# Thetis_RevD2_SCH.net
KiCad netlist of a schematic drawn in EAGLE
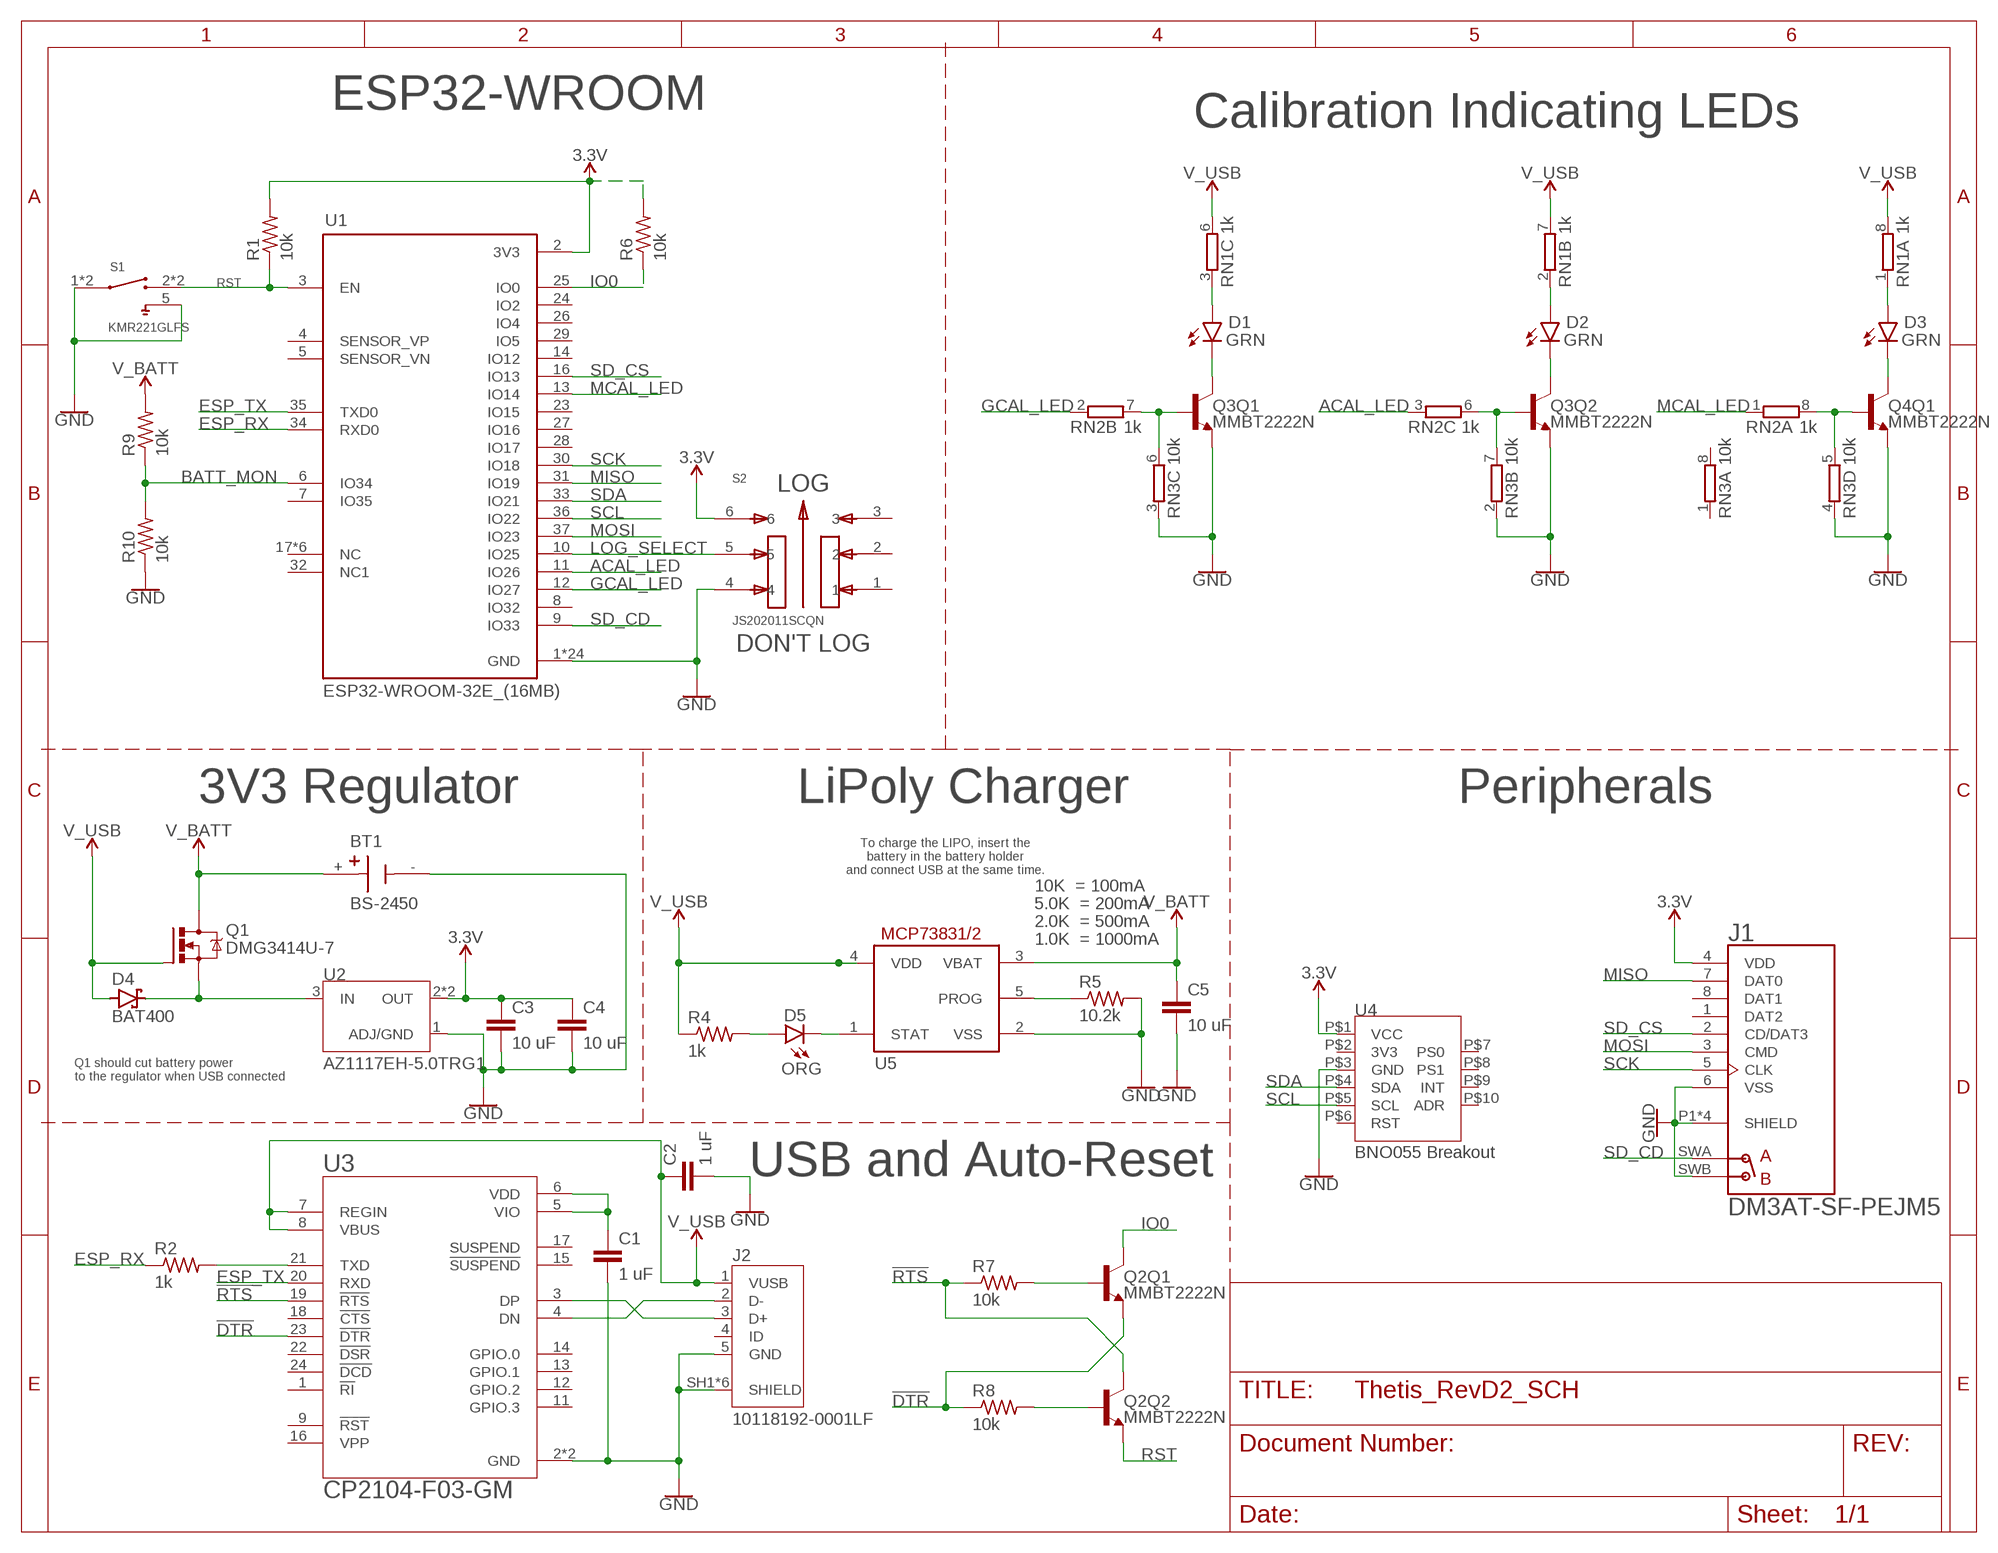
[diagram p0: schematic, sheet 1]

(export (version "E")
  (design (tool "Eeschema 10.0.6"))
  (components
    (comp (ref "BT1")
      (value "BS-2450")
      (footprint "eagle-import:BAT_BS-2450")
      (fields (field (name "MF") "MPD"))
      (libsource (lib "eagle-import") (part "BS-2450"))
    )
    (comp (ref "C1")
      (value "1 uF")
      (footprint "eagle-import:C0603")
      (libsource (lib "eagle-import") (part "C-EUC0603"))
    )
    (comp (ref "C2")
      (value "1 uF")
      (footprint "eagle-import:C0603")
      (libsource (lib "eagle-import") (part "C-EUC0603"))
    )
    (comp (ref "C3")
      (value "10 uF")
      (footprint "eagle-import:C0603")
      (libsource (lib "eagle-import") (part "C-EUC0603"))
    )
    (comp (ref "C4")
      (value "10 uF")
      (footprint "eagle-import:C0603")
      (libsource (lib "eagle-import") (part "C-EUC0603"))
    )
    (comp (ref "C5")
      (value "10 uF")
      (footprint "eagle-import:C0603")
      (libsource (lib "eagle-import") (part "C-EUC0603"))
    )
    (comp (ref "D1")
      (value "GRN")
      (footprint "eagle-import:LEDC1608X65N")
      (libsource (lib "eagle-import") (part "CHIP-ROUND-G_0603"))
    )
    (comp (ref "D2")
      (value "GRN")
      (footprint "eagle-import:LEDC1608X65N")
      (libsource (lib "eagle-import") (part "CHIP-ROUND-G_0603"))
    )
    (comp (ref "D3")
      (value "GRN")
      (footprint "eagle-import:LEDC1608X65N")
      (libsource (lib "eagle-import") (part "CHIP-ROUND-G_0603"))
    )
    (comp (ref "D4")
      (value "BAT400")
      (footprint "eagle-import:SOT23")
      (libsource (lib "eagle-import") (part "BAS40"))
    )
    (comp (ref "D5")
      (value "ORG")
      (footprint "eagle-import:LEDC1608X65N")
      (libsource (lib "eagle-import") (part "CHIP-ROUND-G_0603"))
    )
    (comp (ref "J1")
      (value "DM3AT-SF-PEJM5")
      (footprint "eagle-import:HRS_DM3AT-SF-PEJM5")
      (fields (field (name "MF") "Hirose"))
      (libsource (lib "eagle-import") (part "DM3AT-SF-PEJM5"))
    )
    (comp (ref "J2")
      (value "10118192-0001LF")
      (footprint "eagle-import:AMPHENOL_10118192-0001LF")
      (fields (field (name "MANUFACTURER") "Amphenol"))
      (libsource (lib "eagle-import") (part "10118192-0001LF"))
    )
    (comp (ref "Q1")
      (value "DMG3414U-7")
      (footprint "eagle-import:SOT23")
      (libsource (lib "eagle-import") (part "NMOSFETSOT23"))
    )
    (comp (ref "Q2")
      (value "MMBT2222N")
      (footprint "eagle-import:SC70-6")
      (libsource (lib "eagle-import") (part "TRANS_NPN_DUAL-MBT3904DW1T1"))
    )
    (comp (ref "Q3")
      (value "MMBT2222N")
      (footprint "eagle-import:SC70-6")
      (libsource (lib "eagle-import") (part "TRANS_NPN_DUAL-MBT3904DW1T1"))
    )
    (comp (ref "Q4")
      (value "MMBT2222N")
      (footprint "eagle-import:SC70-6")
      (libsource (lib "eagle-import") (part "TRANS_NPN_DUAL-MBT3904DW1T1"))
    )
    (comp (ref "R1")
      (value "10k")
      (footprint "eagle-import:R0603")
      (libsource (lib "eagle-import") (part "R-US_R0603"))
    )
    (comp (ref "R2")
      (value "1k")
      (footprint "eagle-import:R0603")
      (libsource (lib "eagle-import") (part "R-US_R0603"))
    )
    (comp (ref "R4")
      (value "1k")
      (footprint "eagle-import:R0603")
      (libsource (lib "eagle-import") (part "R-US_R0603"))
    )
    (comp (ref "R5")
      (value "10.2k")
      (footprint "eagle-import:R0603")
      (libsource (lib "eagle-import") (part "R-US_R0603"))
    )
    (comp (ref "R6")
      (value "10k")
      (footprint "eagle-import:R0603")
      (libsource (lib "eagle-import") (part "R-US_R0603"))
    )
    (comp (ref "R7")
      (value "10k")
      (footprint "eagle-import:R0603")
      (libsource (lib "eagle-import") (part "R-US_R0603"))
    )
    (comp (ref "R8")
      (value "10k")
      (footprint "eagle-import:R0603")
      (libsource (lib "eagle-import") (part "R-US_R0603"))
    )
    (comp (ref "R9")
      (value "10k")
      (footprint "eagle-import:R0603")
      (libsource (lib "eagle-import") (part "R-US_R0603"))
    )
    (comp (ref "R10")
      (value "10k")
      (footprint "eagle-import:R0603")
      (libsource (lib "eagle-import") (part "R-US_R0603"))
    )
    (comp (ref "RN1")
      (value "1k")
      (footprint "eagle-import:EXB28V")
      (libsource (lib "eagle-import") (part "4R-NEXB28V"))
    )
    (comp (ref "RN2")
      (value "1k")
      (footprint "eagle-import:EXB28V")
      (libsource (lib "eagle-import") (part "4R-NEXB28V"))
    )
    (comp (ref "RN3")
      (value "10k")
      (footprint "eagle-import:EXB28V")
      (libsource (lib "eagle-import") (part "4R-NEXB28V"))
    )
    (comp (ref "S1")
      (value "KMR221GLFS")
      (footprint "eagle-import:SW_KMR221GLFS")
      (fields (field (name "MANUFACTURER") "CnK"))
      (libsource (lib "eagle-import") (part "KMR221GLFS"))
    )
    (comp (ref "S2")
      (value "JS202011SCQN")
      (footprint "eagle-import:SW_JS202011SCQN")
      (fields (field (name "MANUFACTURER") "C&K"))
      (libsource (lib "eagle-import") (part "JS202011SCQN"))
    )
    (comp (ref "U1")
      (value "ESP32-WROOM-32E_(16MB)")
      (footprint "eagle-import:MODULE_ESP32-WROOM-32E_(16MB)")
      (fields (field (name "MANUFACTURER") "Espressif Systems"))
      (libsource (lib "eagle-import") (part "ESP32-WROOM-32E_(16MB)"))
    )
    (comp (ref "U2")
      (value "AZ1117EH-5.0TRG1")
      (footprint "eagle-import:SOT230P700X180-4N")
      (fields (field (name "MF") "Diodes Inc."))
      (libsource (lib "eagle-import") (part "AZ1117EH-5.0TRG1"))
    )
    (comp (ref "U3")
      (value "CP2104-F03-GM")
      (footprint "eagle-import:QFN50P400X400X80-25N")
      (libsource (lib "eagle-import") (part "CP2104-F03-GM"))
    )
    (comp (ref "U4")
      (value "BNO055 Breakout")
      (footprint "eagle-import:ADAFRUIT-BNO055-BREAKOUT-SMD")
      (libsource (lib "eagle-import") (part "ADAFRUIT-BNO055-BREAKOUT-SMD"))
    )
    (comp (ref "U5")
      (value "MCP73831/OT")
      (footprint "eagle-import:SOT23-5L")
      (libsource (lib "eagle-import") (part "MCP73831/OT"))
    )
  )
  (nets
    (net (code "1") (name "/3V3") (class "Default")
      (node (ref "U4") (pin "P$2") (pinfunction "3V3_P$2") (pintype "power_in"))
    )
    (net (code "2") (name "/ACAL_LED") (class "Default")
      (node (ref "RN2") (pin "3") (pinfunction "1_3") (pintype "passive"))
      (node (ref "U1") (pin "11") (pinfunction "IO26_11") (pintype "bidirectional"))
    )
    (net (code "3") (name "/BATT_MON") (class "Default")
      (node (ref "R10") (pin "2") (pinfunction "2_2") (pintype "passive"))
      (node (ref "R9") (pin "1") (pinfunction "1_1") (pintype "passive"))
      (node (ref "U1") (pin "6") (pinfunction "IO34_6") (pintype "input"))
    )
    (net (code "4") (name "/ESP_RX") (class "Default")
      (node (ref "R2") (pin "1") (pinfunction "1_1") (pintype "passive"))
      (node (ref "U1") (pin "34") (pinfunction "RXD0_34") (pintype "bidirectional"))
    )
    (net (code "5") (name "/ESP_TX") (class "Default")
      (node (ref "U1") (pin "35") (pinfunction "TXD0_35") (pintype "bidirectional"))
      (node (ref "U3") (pin "20") (pinfunction "RXD_20") (pintype "input"))
    )
    (net (code "6") (name "/GCAL_LED") (class "Default")
      (node (ref "RN2") (pin "2") (pinfunction "1_2") (pintype "passive"))
      (node (ref "U1") (pin "12") (pinfunction "IO27_12") (pintype "bidirectional"))
    )
    (net (code "7") (name "/IO0") (class "Default")
      (node (ref "Q2") (pin "3") (pinfunction "C_3") (pintype "passive"))
      (node (ref "R6") (pin "1") (pinfunction "1_1") (pintype "passive"))
      (node (ref "U1") (pin "25") (pinfunction "IO0_25") (pintype "bidirectional"))
    )
    (net (code "8") (name "/LOG_SELECT") (class "Default")
      (node (ref "S2") (pin "5") (pinfunction "5_5") (pintype "passive"))
      (node (ref "U1") (pin "10") (pinfunction "IO25_10") (pintype "bidirectional"))
    )
    (net (code "9") (name "/MCAL_LED") (class "Default")
      (node (ref "RN2") (pin "1") (pinfunction "1_1") (pintype "passive"))
      (node (ref "U1") (pin "13") (pinfunction "IO14_13") (pintype "bidirectional"))
    )
    (net (code "10") (name "/MISO") (class "Default")
      (node (ref "J1") (pin "7") (pinfunction "DAT0_7") (pintype "bidirectional"))
      (node (ref "U1") (pin "31") (pinfunction "IO19_31") (pintype "bidirectional"))
    )
    (net (code "11") (name "/MOSI") (class "Default")
      (node (ref "J1") (pin "3") (pinfunction "CMD_3") (pintype "bidirectional"))
      (node (ref "U1") (pin "37") (pinfunction "IO23_37") (pintype "bidirectional"))
    )
    (net (code "12") (name "/RST") (class "Default")
      (node (ref "Q2") (pin "1") (pinfunction "E_1") (pintype "passive"))
      (node (ref "R1") (pin "1") (pinfunction "1_1") (pintype "passive"))
      (node (ref "S1") (pin "2") (pinfunction "3_2") (pintype "passive"))
      (node (ref "S1") (pin "3") (pinfunction "3_3") (pintype "passive"))
      (node (ref "U1") (pin "3") (pinfunction "EN_3") (pintype "input"))
    )
    (net (code "13") (name "/SCK") (class "Default")
      (node (ref "J1") (pin "5") (pinfunction "CLK_5") (pintype "bidirectional"))
      (node (ref "U1") (pin "30") (pinfunction "IO18_30") (pintype "bidirectional"))
    )
    (net (code "14") (name "/SCL") (class "Default")
      (node (ref "U1") (pin "36") (pinfunction "IO22_36") (pintype "bidirectional"))
      (node (ref "U4") (pin "P$5") (pinfunction "SCL_P$5") (pintype "bidirectional"))
    )
    (net (code "15") (name "/SDA") (class "Default")
      (node (ref "U1") (pin "33") (pinfunction "IO21_33") (pintype "bidirectional"))
      (node (ref "U4") (pin "P$4") (pinfunction "SDA_P$4") (pintype "bidirectional"))
    )
    (net (code "16") (name "/SD_CD") (class "Default")
      (node (ref "J1") (pin "SWA") (pinfunction "A_SWA") (pintype "bidirectional"))
      (node (ref "U1") (pin "9") (pinfunction "IO33_9") (pintype "bidirectional"))
    )
    (net (code "17") (name "/SD_CS") (class "Default")
      (node (ref "J1") (pin "2") (pinfunction "CD/DAT3_2") (pintype "bidirectional"))
      (node (ref "U1") (pin "16") (pinfunction "IO13_16") (pintype "bidirectional"))
    )
    (net (code "18") (name "/~{DTR}") (class "Default")
      (node (ref "Q2") (pin "4") (pinfunction "E_4") (pintype "passive"))
      (node (ref "R8") (pin "1") (pinfunction "1_1") (pintype "passive"))
      (node (ref "U3") (pin "23") (pinfunction "~{DTR}_23") (pintype "output"))
    )
    (net (code "19") (name "/~{RTS}") (class "Default")
      (node (ref "Q2") (pin "6") (pinfunction "C_6") (pintype "passive"))
      (node (ref "R7") (pin "1") (pinfunction "1_1") (pintype "passive"))
      (node (ref "U3") (pin "19") (pinfunction "~{RTS}_19") (pintype "output"))
    )
    (net (code "20") (name "3.3V") (class "Default")
      (node (ref "C3") (pin "1") (pinfunction "1_1") (pintype "passive"))
      (node (ref "C4") (pin "1") (pinfunction "1_1") (pintype "passive"))
      (node (ref "J1") (pin "4") (pinfunction "VDD_4") (pintype "power_in"))
      (node (ref "R1") (pin "2") (pinfunction "2_2") (pintype "passive"))
      (node (ref "R6") (pin "2") (pinfunction "2_2") (pintype "passive"))
      (node (ref "S2") (pin "6") (pinfunction "6_6") (pintype "passive"))
      (node (ref "U1") (pin "2") (pinfunction "3V3_2") (pintype "power_in"))
      (node (ref "U2") (pin "2") (pinfunction "OUT_2") (pintype "output"))
      (node (ref "U2") (pin "4") (pinfunction "OUT_4") (pintype "output"))
      (node (ref "U4") (pin "P$1") (pinfunction "VCC_P$1") (pintype "power_in"))
    )
    (net (code "21") (name "GND") (class "Default")
      (node (ref "BT1") (pin "-") (pinfunction "-_-") (pintype "passive"))
      (node (ref "C1") (pin "2") (pinfunction "2_2") (pintype "passive"))
      (node (ref "C2") (pin "2") (pinfunction "2_2") (pintype "passive"))
      (node (ref "C3") (pin "2") (pinfunction "2_2") (pintype "passive"))
      (node (ref "C4") (pin "2") (pinfunction "2_2") (pintype "passive"))
      (node (ref "C5") (pin "2") (pinfunction "2_2") (pintype "passive"))
      (node (ref "J1") (pin "6") (pinfunction "VSS_6") (pintype "power_in"))
      (node (ref "J1") (pin "P1") (pinfunction "SHIELD_P1") (pintype "passive"))
      (node (ref "J1") (pin "P2") (pinfunction "SHIELD_P2") (pintype "passive"))
      (node (ref "J1") (pin "P3") (pinfunction "SHIELD_P3") (pintype "passive"))
      (node (ref "J1") (pin "P4") (pinfunction "SHIELD_P4") (pintype "passive"))
      (node (ref "J1") (pin "SWB") (pinfunction "B_SWB") (pintype "bidirectional"))
      (node (ref "J2") (pin "5") (pinfunction "GND_5") (pintype "passive"))
      (node (ref "J2") (pin "SH1") (pinfunction "SHIELD_SH1") (pintype "passive"))
      (node (ref "J2") (pin "SH2") (pinfunction "SHIELD_SH2") (pintype "passive"))
      (node (ref "J2") (pin "SH3") (pinfunction "SHIELD_SH3") (pintype "passive"))
      (node (ref "J2") (pin "SH4") (pinfunction "SHIELD_SH4") (pintype "passive"))
      (node (ref "J2") (pin "SH5") (pinfunction "SHIELD_SH5") (pintype "passive"))
      (node (ref "J2") (pin "SH6") (pinfunction "SHIELD_SH6") (pintype "passive"))
      (node (ref "Q3") (pin "1") (pinfunction "E_1") (pintype "passive"))
      (node (ref "Q3") (pin "4") (pinfunction "E_4") (pintype "passive"))
      (node (ref "Q4") (pin "4") (pinfunction "E_4") (pintype "passive"))
      (node (ref "R10") (pin "1") (pinfunction "1_1") (pintype "passive"))
      (node (ref "R5") (pin "2") (pinfunction "2_2") (pintype "passive"))
      (node (ref "RN3") (pin "2") (pinfunction "1_2") (pintype "passive"))
      (node (ref "RN3") (pin "3") (pinfunction "1_3") (pintype "passive"))
      (node (ref "RN3") (pin "4") (pinfunction "1_4") (pintype "passive"))
      (node (ref "S1") (pin "1") (pinfunction "1_1") (pintype "passive"))
      (node (ref "S1") (pin "4") (pinfunction "1_4") (pintype "passive"))
      (node (ref "S1") (pin "5") (pinfunction "5_5") (pintype "passive"))
      (node (ref "S2") (pin "4") (pinfunction "4_4") (pintype "passive"))
      (node (ref "U1") (pin "1") (pinfunction "GND_1") (pintype "power_in"))
      (node (ref "U1") (pin "15") (pinfunction "GND_15") (pintype "power_in"))
      (node (ref "U1") (pin "38") (pinfunction "GND_38") (pintype "power_in"))
      (node (ref "U1") (pin "39_1") (pinfunction "GND_39_1") (pintype "power_in"))
      (node (ref "U1") (pin "39_10") (pinfunction "GND_39_10") (pintype "power_in"))
      (node (ref "U1") (pin "39_11") (pinfunction "GND_39_11") (pintype "power_in"))
      (node (ref "U1") (pin "39_12") (pinfunction "GND_39_12") (pintype "power_in"))
      (node (ref "U1") (pin "39_13") (pinfunction "GND_39_13") (pintype "power_in"))
      (node (ref "U1") (pin "39_14") (pinfunction "GND_39_14") (pintype "power_in"))
      (node (ref "U1") (pin "39_15") (pinfunction "GND_39_15") (pintype "power_in"))
      (node (ref "U1") (pin "39_16") (pinfunction "GND_39_16") (pintype "power_in"))
      (node (ref "U1") (pin "39_17") (pinfunction "GND_39_17") (pintype "power_in"))
      (node (ref "U1") (pin "39_18") (pinfunction "GND_39_18") (pintype "power_in"))
      (node (ref "U1") (pin "39_19") (pinfunction "GND_39_19") (pintype "power_in"))
      (node (ref "U1") (pin "39_2") (pinfunction "GND_39_2") (pintype "power_in"))
      (node (ref "U1") (pin "39_20") (pinfunction "GND_39_20") (pintype "power_in"))
      (node (ref "U1") (pin "39_21") (pinfunction "GND_39_21") (pintype "power_in"))
      (node (ref "U1") (pin "39_3") (pinfunction "GND_39_3") (pintype "power_in"))
      (node (ref "U1") (pin "39_4") (pinfunction "GND_39_4") (pintype "power_in"))
      (node (ref "U1") (pin "39_5") (pinfunction "GND_39_5") (pintype "power_in"))
      (node (ref "U1") (pin "39_6") (pinfunction "GND_39_6") (pintype "power_in"))
      (node (ref "U1") (pin "39_7") (pinfunction "GND_39_7") (pintype "power_in"))
      (node (ref "U1") (pin "39_8") (pinfunction "GND_39_8") (pintype "power_in"))
      (node (ref "U1") (pin "39_9") (pinfunction "GND_39_9") (pintype "power_in"))
      (node (ref "U2") (pin "1") (pinfunction "ADJ/GND_1") (pintype "power_in"))
      (node (ref "U3") (pin "2") (pinfunction "GND_2") (pintype "power_in"))
      (node (ref "U3") (pin "25") (pinfunction "GND_25") (pintype "power_in"))
      (node (ref "U4") (pin "P$3") (pinfunction "GND_P$3") (pintype "power_in"))
      (node (ref "U5") (pin "2") (pinfunction "VSS_2") (pintype "power_in"))
    )
    (net (code "22") (name "Net-(D3-PadA)") (class "Default")
      (node (ref "D3") (pin "A") (pinfunction "A_A") (pintype "passive"))
      (node (ref "RN1") (pin "1") (pinfunction "1_1") (pintype "passive"))
    )
    (net (code "23") (name "Net-(D4-C)") (class "Default")
      (node (ref "D4") (pin "3") (pinfunction "C_3") (pintype "passive"))
      (node (ref "Q1") (pin "2") (pinfunction "S_2") (pintype "passive"))
      (node (ref "U2") (pin "3") (pinfunction "IN_3") (pintype "input"))
    )
    (net (code "24") (name "Net-(D5-PadA)") (class "Default")
      (node (ref "D5") (pin "A") (pinfunction "A_A") (pintype "passive"))
      (node (ref "R4") (pin "2") (pinfunction "2_2") (pintype "passive"))
    )
    (net (code "25") (name "Net-(J2-D+)") (class "Default")
      (node (ref "J2") (pin "3") (pinfunction "D+_3") (pintype "passive"))
      (node (ref "U3") (pin "3") (pinfunction "DP_3") (pintype "bidirectional"))
    )
    (net (code "26") (name "Net-(J2-D-)") (class "Default")
      (node (ref "J2") (pin "2") (pinfunction "D-_2") (pintype "passive"))
      (node (ref "U3") (pin "4") (pinfunction "DN_4") (pintype "bidirectional"))
    )
    (net (code "27") (name "Net-(Q2A-B)") (class "Default")
      (node (ref "Q2") (pin "5") (pinfunction "B_5") (pintype "passive"))
      (node (ref "R7") (pin "2") (pinfunction "2_2") (pintype "passive"))
    )
    (net (code "28") (name "Net-(Q2B-B)") (class "Default")
      (node (ref "Q2") (pin "2") (pinfunction "B_2") (pintype "passive"))
      (node (ref "R8") (pin "2") (pinfunction "2_2") (pintype "passive"))
    )
    (net (code "29") (name "Net-(Q3A-B)") (class "Default")
      (node (ref "Q3") (pin "5") (pinfunction "B_5") (pintype "passive"))
      (node (ref "RN2") (pin "7") (pinfunction "2_7") (pintype "passive"))
      (node (ref "RN3") (pin "6") (pinfunction "2_6") (pintype "passive"))
    )
    (net (code "30") (name "Net-(Q3A-C)") (class "Default")
      (node (ref "D1") (pin "C") (pinfunction "C_C") (pintype "passive"))
      (node (ref "Q3") (pin "3") (pinfunction "C_3") (pintype "passive"))
    )
    (net (code "31") (name "Net-(Q3B-B)") (class "Default")
      (node (ref "Q3") (pin "2") (pinfunction "B_2") (pintype "passive"))
      (node (ref "RN2") (pin "6") (pinfunction "2_6") (pintype "passive"))
      (node (ref "RN3") (pin "7") (pinfunction "2_7") (pintype "passive"))
    )
    (net (code "32") (name "Net-(Q3B-C)") (class "Default")
      (node (ref "D2") (pin "C") (pinfunction "C_C") (pintype "passive"))
      (node (ref "Q3") (pin "6") (pinfunction "C_6") (pintype "passive"))
    )
    (net (code "33") (name "Net-(Q4A-B)") (class "Default")
      (node (ref "Q4") (pin "5") (pinfunction "B_5") (pintype "passive"))
      (node (ref "RN2") (pin "8") (pinfunction "2_8") (pintype "passive"))
      (node (ref "RN3") (pin "5") (pinfunction "2_5") (pintype "passive"))
    )
    (net (code "34") (name "Net-(Q4A-C)") (class "Default")
      (node (ref "D3") (pin "C") (pinfunction "C_C") (pintype "passive"))
      (node (ref "Q4") (pin "3") (pinfunction "C_3") (pintype "passive"))
    )
    (net (code "35") (name "Net-(RN1B-1)") (class "Default")
      (node (ref "D2") (pin "A") (pinfunction "A_A") (pintype "passive"))
      (node (ref "RN1") (pin "2") (pinfunction "1_2") (pintype "passive"))
    )
    (net (code "36") (name "Net-(RN1C-1)") (class "Default")
      (node (ref "D1") (pin "A") (pinfunction "A_A") (pintype "passive"))
      (node (ref "RN1") (pin "3") (pinfunction "1_3") (pintype "passive"))
    )
    (net (code "37") (name "Net-(U3-TXD)") (class "Default")
      (node (ref "R2") (pin "2") (pinfunction "2_2") (pintype "passive"))
      (node (ref "U3") (pin "21") (pinfunction "TXD_21") (pintype "output"))
    )
    (net (code "38") (name "Net-(U3-VDD)") (class "Default")
      (node (ref "C1") (pin "1") (pinfunction "1_1") (pintype "passive"))
      (node (ref "U3") (pin "5") (pinfunction "VIO_5") (pintype "power_in"))
      (node (ref "U3") (pin "6") (pinfunction "VDD_6") (pintype "power_in"))
    )
    (net (code "39") (name "Net-(U5-PROG)") (class "Default")
      (node (ref "R5") (pin "1") (pinfunction "1_1") (pintype "passive"))
      (node (ref "U5") (pin "5") (pinfunction "PROG_5") (pintype "input"))
    )
    (net (code "40") (name "Net-(U5-STAT)") (class "Default")
      (node (ref "D5") (pin "C") (pinfunction "C_C") (pintype "passive"))
      (node (ref "U5") (pin "1") (pinfunction "STAT_1") (pintype "output"))
    )
    (net (code "41") (name "V_BATT") (class "Default")
      (node (ref "BT1") (pin "+") (pinfunction "+_+") (pintype "passive"))
      (node (ref "C5") (pin "1") (pinfunction "1_1") (pintype "passive"))
      (node (ref "Q1") (pin "3") (pinfunction "D_3") (pintype "passive"))
      (node (ref "R9") (pin "2") (pinfunction "2_2") (pintype "passive"))
      (node (ref "U5") (pin "3") (pinfunction "VBAT_3") (pintype "bidirectional"))
    )
    (net (code "42") (name "V_USB") (class "Default")
      (node (ref "C2") (pin "1") (pinfunction "1_1") (pintype "passive"))
      (node (ref "D4") (pin "1") (pinfunction "A_1") (pintype "passive"))
      (node (ref "J2") (pin "1") (pinfunction "VUSB_1") (pintype "passive"))
      (node (ref "Q1") (pin "1") (pinfunction "G_1") (pintype "passive"))
      (node (ref "R4") (pin "1") (pinfunction "1_1") (pintype "passive"))
      (node (ref "RN1") (pin "6") (pinfunction "2_6") (pintype "passive"))
      (node (ref "RN1") (pin "7") (pinfunction "2_7") (pintype "passive"))
      (node (ref "RN1") (pin "8") (pinfunction "2_8") (pintype "passive"))
      (node (ref "U3") (pin "7") (pinfunction "REGIN_7") (pintype "input"))
      (node (ref "U3") (pin "8") (pinfunction "VBUS_8") (pintype "input"))
      (node (ref "U5") (pin "4") (pinfunction "VDD_4") (pintype "power_in"))
    )
    (net (code "43") (name "unconnected-(J1-DAT1-Pad8)") (class "Default")
      (node (ref "J1") (pin "8") (pinfunction "DAT1_8") (pintype "bidirectional"))
    )
    (net (code "44") (name "unconnected-(J1-DAT2-Pad1)") (class "Default")
      (node (ref "J1") (pin "1") (pinfunction "DAT2_1") (pintype "bidirectional"))
    )
    (net (code "45") (name "unconnected-(J2-ID-Pad4)") (class "Default")
      (node (ref "J2") (pin "4") (pinfunction "ID_4") (pintype "passive"))
    )
    (net (code "46") (name "unconnected-(RN3-Pad1)") (class "Default")
      (node (ref "RN3") (pin "1") (pinfunction "1_1") (pintype "passive"))
    )
    (net (code "47") (name "unconnected-(RN3A-2-Pad8)") (class "Default")
      (node (ref "RN3") (pin "8") (pinfunction "2_8") (pintype "passive"))
    )
    (net (code "48") (name "unconnected-(S2-Pad1)") (class "Default")
      (node (ref "S2") (pin "1") (pinfunction "1_1") (pintype "passive"))
    )
    (net (code "49") (name "unconnected-(S2-Pad2)") (class "Default")
      (node (ref "S2") (pin "2") (pinfunction "2_2") (pintype "passive"))
    )
    (net (code "50") (name "unconnected-(S2-Pad3)") (class "Default")
      (node (ref "S2") (pin "3") (pinfunction "3_3") (pintype "passive"))
    )
    (net (code "51") (name "unconnected-(U1-IO2-Pad24)") (class "Default")
      (node (ref "U1") (pin "24") (pinfunction "IO2_24") (pintype "bidirectional"))
    )
    (net (code "52") (name "unconnected-(U1-IO4-Pad26)") (class "Default")
      (node (ref "U1") (pin "26") (pinfunction "IO4_26") (pintype "bidirectional"))
    )
    (net (code "53") (name "unconnected-(U1-IO5-Pad29)") (class "Default")
      (node (ref "U1") (pin "29") (pinfunction "IO5_29") (pintype "bidirectional"))
    )
    (net (code "54") (name "unconnected-(U1-IO12-Pad14)") (class "Default")
      (node (ref "U1") (pin "14") (pinfunction "IO12_14") (pintype "bidirectional"))
    )
    (net (code "55") (name "unconnected-(U1-IO15-Pad23)") (class "Default")
      (node (ref "U1") (pin "23") (pinfunction "IO15_23") (pintype "bidirectional"))
    )
    (net (code "56") (name "unconnected-(U1-IO16-Pad27)") (class "Default")
      (node (ref "U1") (pin "27") (pinfunction "IO16_27") (pintype "bidirectional"))
    )
    (net (code "57") (name "unconnected-(U1-IO17-Pad28)") (class "Default")
      (node (ref "U1") (pin "28") (pinfunction "IO17_28") (pintype "bidirectional"))
    )
    (net (code "58") (name "unconnected-(U1-IO32-Pad8)") (class "Default")
      (node (ref "U1") (pin "8") (pinfunction "IO32_8") (pintype "bidirectional"))
    )
    (net (code "59") (name "unconnected-(U1-IO35-Pad7)") (class "Default")
      (node (ref "U1") (pin "7") (pinfunction "IO35_7") (pintype "input"))
    )
    (net (code "60") (name "unconnected-(U1-NC-Pad17)") (class "Default")
      (node (ref "U1") (pin "17") (pinfunction "NC_17") (pintype "no_connect"))
    )
    (net (code "61") (name "unconnected-(U1-NC-Pad18)") (class "Default")
      (node (ref "U1") (pin "18") (pinfunction "NC_18") (pintype "no_connect"))
    )
    (net (code "62") (name "unconnected-(U1-NC-Pad19)") (class "Default")
      (node (ref "U1") (pin "19") (pinfunction "NC_19") (pintype "no_connect"))
    )
    (net (code "63") (name "unconnected-(U1-NC-Pad20)") (class "Default")
      (node (ref "U1") (pin "20") (pinfunction "NC_20") (pintype "no_connect"))
    )
    (net (code "64") (name "unconnected-(U1-NC-Pad21)") (class "Default")
      (node (ref "U1") (pin "21") (pinfunction "NC_21") (pintype "no_connect"))
    )
    (net (code "65") (name "unconnected-(U1-NC-Pad22)") (class "Default")
      (node (ref "U1") (pin "22") (pinfunction "NC_22") (pintype "no_connect"))
    )
    (net (code "66") (name "unconnected-(U1-NC1-Pad32)") (class "Default")
      (node (ref "U1") (pin "32") (pinfunction "NC1_32") (pintype "no_connect"))
    )
    (net (code "67") (name "unconnected-(U1-SENSOR_VN-Pad5)") (class "Default")
      (node (ref "U1") (pin "5") (pinfunction "SENSOR_VN_5") (pintype "input"))
    )
    (net (code "68") (name "unconnected-(U1-SENSOR_VP-Pad4)") (class "Default")
      (node (ref "U1") (pin "4") (pinfunction "SENSOR_VP_4") (pintype "input"))
    )
    (net (code "69") (name "unconnected-(U3-GPIO.0-Pad14)") (class "Default")
      (node (ref "U3") (pin "14") (pinfunction "GPIO.0_14") (pintype "bidirectional"))
    )
    (net (code "70") (name "unconnected-(U3-GPIO.1-Pad13)") (class "Default")
      (node (ref "U3") (pin "13") (pinfunction "GPIO.1_13") (pintype "bidirectional"))
    )
    (net (code "71") (name "unconnected-(U3-GPIO.2-Pad12)") (class "Default")
      (node (ref "U3") (pin "12") (pinfunction "GPIO.2_12") (pintype "bidirectional"))
    )
    (net (code "72") (name "unconnected-(U3-GPIO.3-Pad11)") (class "Default")
      (node (ref "U3") (pin "11") (pinfunction "GPIO.3_11") (pintype "bidirectional"))
    )
    (net (code "73") (name "unconnected-(U3-SUSPEND-Pad17)") (class "Default")
      (node (ref "U3") (pin "17") (pinfunction "SUSPEND_17") (pintype "output"))
    )
    (net (code "74") (name "unconnected-(U3-VPP-Pad16)") (class "Default")
      (node (ref "U3") (pin "16") (pinfunction "VPP_16") (pintype "passive"))
    )
    (net (code "75") (name "unconnected-(U3-~{CTS}-Pad18)") (class "Default")
      (node (ref "U3") (pin "18") (pinfunction "~{CTS}_18") (pintype "input"))
    )
    (net (code "76") (name "unconnected-(U3-~{DCD}-Pad24)") (class "Default")
      (node (ref "U3") (pin "24") (pinfunction "~{DCD}_24") (pintype "input"))
    )
    (net (code "77") (name "unconnected-(U3-~{DSR}-Pad22)") (class "Default")
      (node (ref "U3") (pin "22") (pinfunction "~{DSR}_22") (pintype "input"))
    )
    (net (code "78") (name "unconnected-(U3-~{RI}-Pad1)") (class "Default")
      (node (ref "U3") (pin "1") (pinfunction "~{RI}_1") (pintype "input"))
    )
    (net (code "79") (name "unconnected-(U3-~{RST}-Pad9)") (class "Default")
      (node (ref "U3") (pin "9") (pinfunction "~{RST}_9") (pintype "bidirectional"))
    )
    (net (code "80") (name "unconnected-(U3-~{SUSPEND}-Pad15)") (class "Default")
      (node (ref "U3") (pin "15") (pinfunction "~{SUSPEND}_15") (pintype "output"))
    )
    (net (code "81") (name "unconnected-(U4-ADR-PadP$10)") (class "Default")
      (node (ref "U4") (pin "P$10") (pinfunction "ADR_P$10") (pintype "bidirectional"))
    )
    (net (code "82") (name "unconnected-(U4-INT-PadP$9)") (class "Default")
      (node (ref "U4") (pin "P$9") (pinfunction "INT_P$9") (pintype "bidirectional"))
    )
    (net (code "83") (name "unconnected-(U4-PS0-PadP$7)") (class "Default")
      (node (ref "U4") (pin "P$7") (pinfunction "PS0_P$7") (pintype "bidirectional"))
    )
    (net (code "84") (name "unconnected-(U4-PS1-PadP$8)") (class "Default")
      (node (ref "U4") (pin "P$8") (pinfunction "PS1_P$8") (pintype "bidirectional"))
    )
    (net (code "85") (name "unconnected-(U4-RST-PadP$6)") (class "Default")
      (node (ref "U4") (pin "P$6") (pinfunction "RST_P$6") (pintype "input"))
    )
  )
)
